# OpenLog.net
KiCad netlist of a schematic drawn in EAGLE
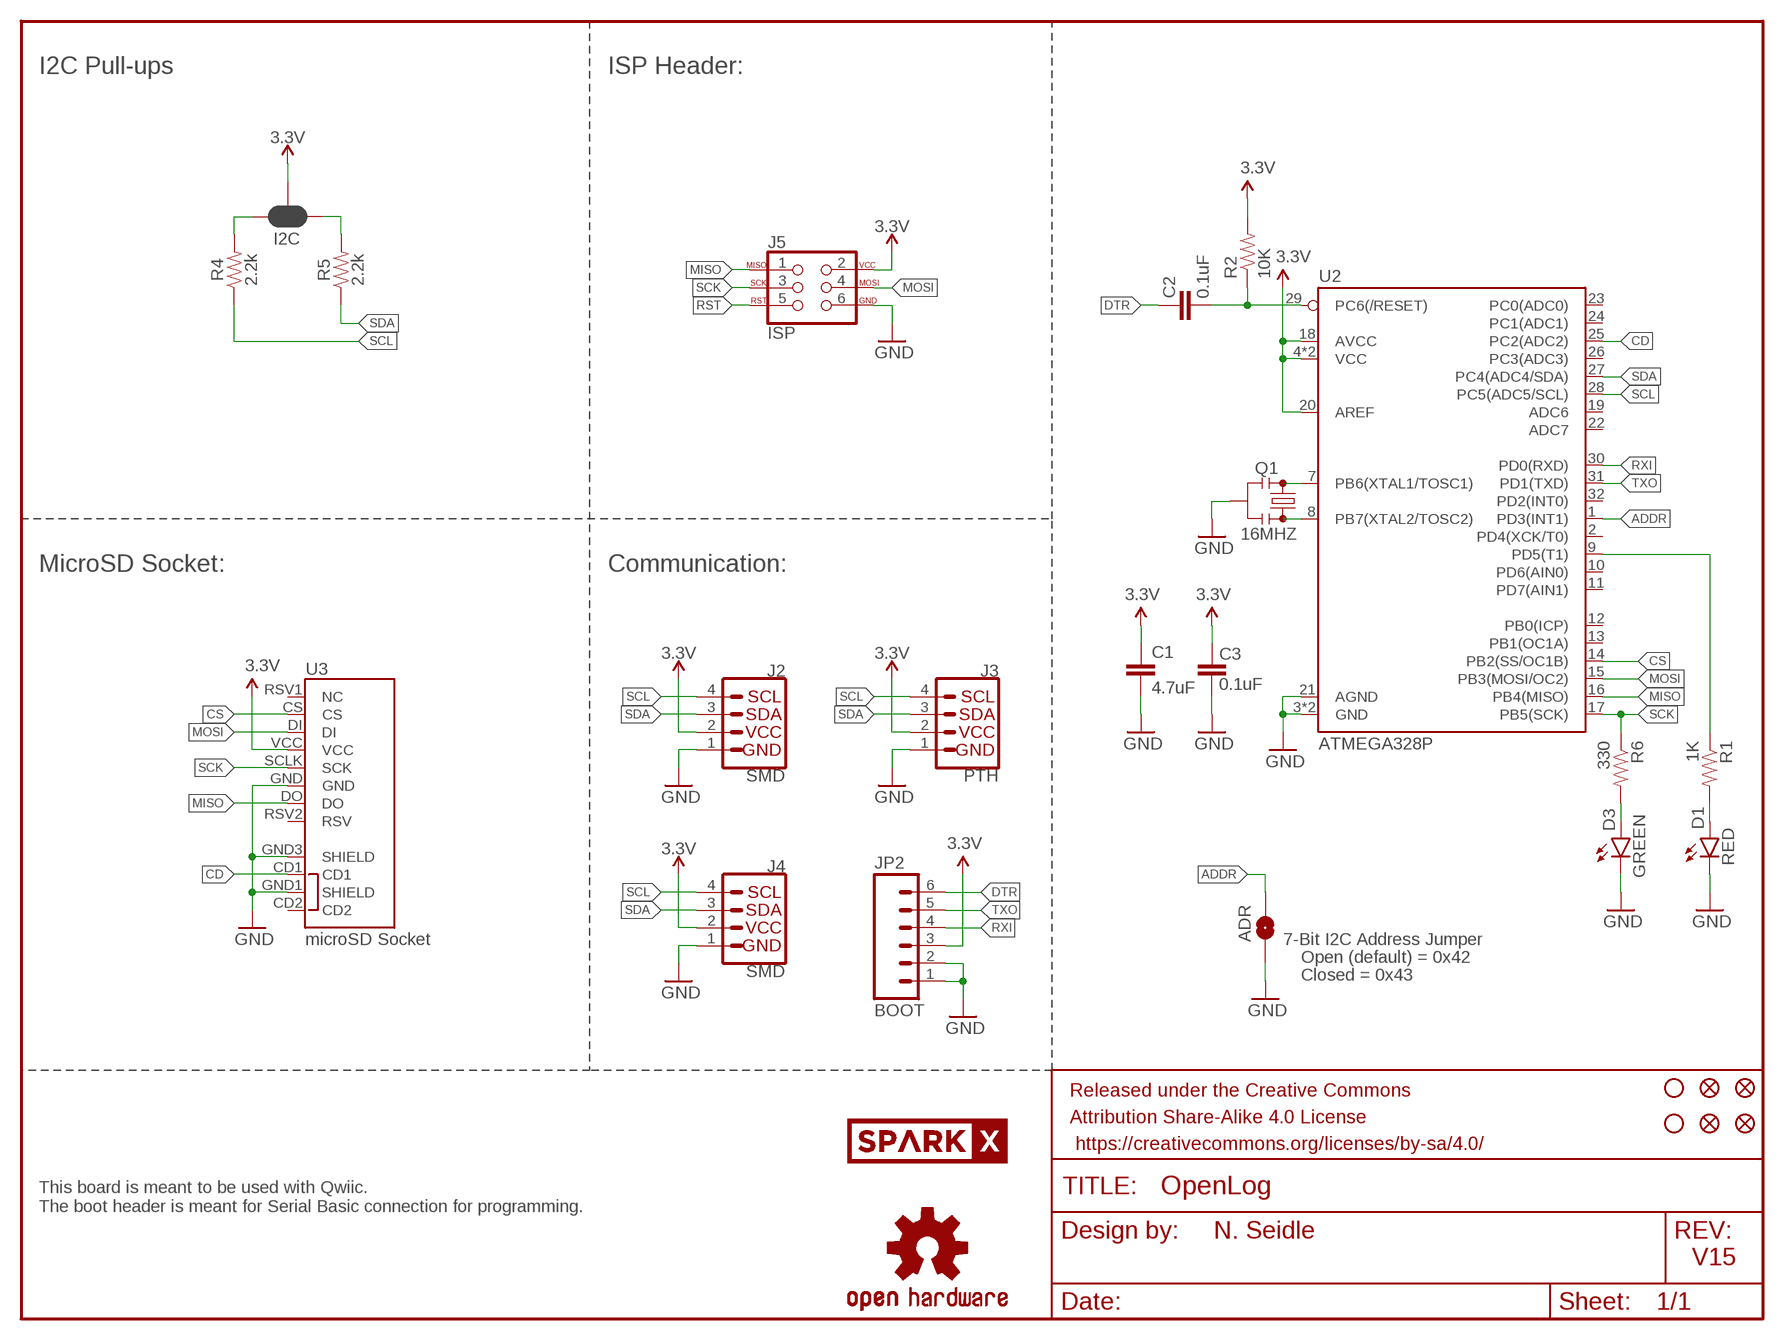
[diagram p0: schematic, sheet 1]

(export (version "E")
  (design (tool "Eeschema 10.0.6"))
  (components
    (comp (ref "ADR")
      (value "SOLDERJUMPERNO")
      (footprint "eagle-import:SJ_2S-NO")
      (libsource (lib "eagle-import") (part "SOLDERJUMPERNO"))
    )
    (comp (ref "C1")
      (value "4.7uF")
      (footprint "eagle-import:0603")
      (libsource (lib "eagle-import") (part "4.7UF0603"))
    )
    (comp (ref "C2")
      (value "0.1uF")
      (footprint "eagle-import:0603-CAP")
      (libsource (lib "eagle-import") (part "0.1UF-25V(+80/-20%)(0603)"))
    )
    (comp (ref "C3")
      (value "0.1uF")
      (footprint "eagle-import:0603-CAP")
      (libsource (lib "eagle-import") (part "0.1UF-25V(+80/-20%)(0603)"))
    )
    (comp (ref "D1")
      (value "RED")
      (footprint "eagle-import:LED-0603")
      (libsource (lib "eagle-import") (part "LED-RED0603"))
    )
    (comp (ref "D3")
      (value "GREEN")
      (footprint "eagle-import:LED-0603")
      (libsource (lib "eagle-import") (part "LED-GREEN0603"))
    )
    (comp (ref "FID1")
      (value "FIDUCIALUFIDUCIAL")
      (footprint "eagle-import:MICRO-FIDUCIAL")
      (libsource (lib "eagle-import") (part "FIDUCIALUFIDUCIAL"))
    )
    (comp (ref "FID2")
      (value "FIDUCIALUFIDUCIAL")
      (footprint "eagle-import:MICRO-FIDUCIAL")
      (libsource (lib "eagle-import") (part "FIDUCIALUFIDUCIAL"))
    )
    (comp (ref "FID3")
      (value "FIDUCIALUFIDUCIAL")
      (footprint "eagle-import:MICRO-FIDUCIAL")
      (libsource (lib "eagle-import") (part "FIDUCIALUFIDUCIAL"))
    )
    (comp (ref "FID4")
      (value "FIDUCIALUFIDUCIAL")
      (footprint "eagle-import:MICRO-FIDUCIAL")
      (libsource (lib "eagle-import") (part "FIDUCIALUFIDUCIAL"))
    )
    (comp (ref "FRAME1")
      (value "FRAME-LETTER")
      (footprint "eagle-import:CREATIVE_COMMONS")
      (libsource (lib "eagle-import") (part "FRAME-LETTER"))
    )
    (comp (ref "I2C")
      (value "JUMPER-SMT_3_2-NC_PASTE_SILK")
      (footprint "eagle-import:SMT-JUMPER_3_2-NC_PASTE_SILK")
      (libsource (lib "eagle-import") (part "JUMPER-SMT_3_2-NC_PASTE_SILK"))
    )
    (comp (ref "J2")
      (value "SMD")
      (footprint "eagle-import:1X04_1MM_RA")
      (libsource (lib "eagle-import") (part "QWIIC_CONNECTORJS-1MM"))
    )
    (comp (ref "J3")
      (value "PTH")
      (footprint "eagle-import:1X04_NO_SILK")
      (libsource (lib "eagle-import") (part "I2C_STANDARD_NO_SILK"))
    )
    (comp (ref "J4")
      (value "SMD")
      (footprint "eagle-import:1X04_1MM_RA")
      (libsource (lib "eagle-import") (part "QWIIC_CONNECTORJS-1MM"))
    )
    (comp (ref "J5")
      (value "ISP")
      (footprint "eagle-import:2X3_TEST_POINTS")
      (libsource (lib "eagle-import") (part "AVR_SPI_PROG_3X2TESTPOINTS"))
    )
    (comp (ref "JP2")
      (value "BOOT")
      (footprint "eagle-import:1X06_NO_SILK")
      (libsource (lib "eagle-import") (part "M06NO_SILK_FEMALE_PTH"))
    )
    (comp (ref "JP3")
      (value "STAND-OFF")
      (footprint "eagle-import:STAND-OFF")
      (libsource (lib "eagle-import") (part "STAND-OFF"))
    )
    (comp (ref "JP4")
      (value "STAND-OFF")
      (footprint "eagle-import:STAND-OFF")
      (libsource (lib "eagle-import") (part "STAND-OFF"))
    )
    (comp (ref "LOGO2")
      (value "OSHW-LOGOMINI")
      (footprint "eagle-import:OSHW-LOGO-MINI")
      (libsource (lib "eagle-import") (part "OSHW-LOGOMINI"))
    )
    (comp (ref "Q1")
      (value "16MHZ")
      (footprint "eagle-import:RESONATOR-SMD")
      (libsource (lib "eagle-import") (part "RESONATOR16MHZ"))
    )
    (comp (ref "R1")
      (value "1K")
      (footprint "eagle-import:0603-RES")
      (libsource (lib "eagle-import") (part "1KOHM-1/10W-1%(0603)"))
    )
    (comp (ref "R2")
      (value "10K")
      (footprint "eagle-import:0603-RES")
      (libsource (lib "eagle-import") (part "10KOHM-1/10W-1%(0603)0603"))
    )
    (comp (ref "R4")
      (value "2.2k")
      (footprint "eagle-import:0603")
      (libsource (lib "eagle-import") (part "2.2KOHM-0603-1/10W-1%"))
    )
    (comp (ref "R5")
      (value "2.2k")
      (footprint "eagle-import:0603")
      (libsource (lib "eagle-import") (part "2.2KOHM-0603-1/10W-1%"))
    )
    (comp (ref "R6")
      (value "330")
      (footprint "eagle-import:0603-RES")
      (libsource (lib "eagle-import") (part "330OHM1/10W1%(0603)"))
    )
    (comp (ref "U$1")
      (value "SPARKX-LOGO4")
      (footprint "eagle-import:SPARKX-MEDIUM")
      (libsource (lib "eagle-import") (part "SPARKX-LOGO4"))
    )
    (comp (ref "U$2")
      (value "SPARKX-LOGO3")
      (footprint "eagle-import:SPARKX-SMALL")
      (libsource (lib "eagle-import") (part "SPARKX-LOGO3"))
    )
    (comp (ref "U2")
      (value "ATMEGA328P")
      (footprint "eagle-import:TQFP32-08")
      (libsource (lib "eagle-import") (part "ATMEGA328P_TQFP"))
    )
    (comp (ref "U3")
      (value "microSD Socket")
      (footprint "eagle-import:MICRO-SD-SOCKET-PP")
      (libsource (lib "eagle-import") (part "MICRO_SD_SOCKETNEW"))
    )
  )
  (nets
    (net (code "1") (name "3.3V") (class "Default")
      (node (ref "C1") (pin "1") (pinfunction "1_1") (pintype "passive"))
      (node (ref "C3") (pin "2") (pinfunction "2_2") (pintype "passive"))
      (node (ref "I2C") (pin "2") (pinfunction "2_2") (pintype "passive"))
      (node (ref "J2") (pin "2") (pinfunction "2_2") (pintype "power_in"))
      (node (ref "J3") (pin "2") (pinfunction "VCC_2") (pintype "power_in"))
      (node (ref "J4") (pin "2") (pinfunction "2_2") (pintype "power_in"))
      (node (ref "J5") (pin "2") (pinfunction "2_2") (pintype "passive"))
      (node (ref "JP2") (pin "3") (pinfunction "3_3") (pintype "passive"))
      (node (ref "R2") (pin "2") (pinfunction "2_2") (pintype "passive"))
      (node (ref "U2") (pin "18") (pinfunction "AVCC_18") (pintype "bidirectional"))
      (node (ref "U2") (pin "20") (pinfunction "AREF_20") (pintype "bidirectional"))
      (node (ref "U2") (pin "4") (pinfunction "VCC_4") (pintype "bidirectional"))
      (node (ref "U2") (pin "6") (pinfunction "VCC_6") (pintype "bidirectional"))
      (node (ref "U3") (pin "VCC") (pinfunction "VCC_VCC") (pintype "bidirectional"))
    )
    (net (code "2") (name "ADDR") (class "Default")
      (node (ref "ADR") (pin "2") (pinfunction "2_2") (pintype "passive"))
      (node (ref "U2") (pin "1") (pinfunction "PD3(INT1)_1") (pintype "bidirectional"))
    )
    (net (code "3") (name "CD") (class "Default")
      (node (ref "U2") (pin "25") (pinfunction "PC2(ADC2)_25") (pintype "bidirectional"))
      (node (ref "U3") (pin "CD1") (pinfunction "CD1_CD1") (pintype "bidirectional"))
    )
    (net (code "4") (name "CS") (class "Default")
      (node (ref "U2") (pin "14") (pinfunction "PB2(SS/OC1B)_14") (pintype "bidirectional"))
      (node (ref "U3") (pin "CS") (pinfunction "CS_CS") (pintype "bidirectional"))
    )
    (net (code "5") (name "DTR") (class "Default")
      (node (ref "C2") (pin "2") (pinfunction "2_2") (pintype "passive"))
      (node (ref "JP2") (pin "6") (pinfunction "6_6") (pintype "passive"))
    )
    (net (code "6") (name "GND") (class "Default")
      (node (ref "ADR") (pin "1") (pinfunction "1_1") (pintype "passive"))
      (node (ref "C1") (pin "2") (pinfunction "2_2") (pintype "passive"))
      (node (ref "C3") (pin "1") (pinfunction "1_1") (pintype "passive"))
      (node (ref "D1") (pin "C") (pinfunction "C_C") (pintype "passive"))
      (node (ref "D3") (pin "C") (pinfunction "C_C") (pintype "passive"))
      (node (ref "J2") (pin "1") (pinfunction "1_1") (pintype "power_in"))
      (node (ref "J3") (pin "1") (pinfunction "GND_1") (pintype "power_in"))
      (node (ref "J4") (pin "1") (pinfunction "1_1") (pintype "power_in"))
      (node (ref "J5") (pin "6") (pinfunction "6_6") (pintype "passive"))
      (node (ref "JP2") (pin "1") (pinfunction "1_1") (pintype "passive"))
      (node (ref "JP2") (pin "2") (pinfunction "2_2") (pintype "passive"))
      (node (ref "Q1") (pin "2") (pinfunction "2_2") (pintype "passive"))
      (node (ref "U2") (pin "21") (pinfunction "AGND_21") (pintype "bidirectional"))
      (node (ref "U2") (pin "3") (pinfunction "GND_3") (pintype "bidirectional"))
      (node (ref "U2") (pin "5") (pinfunction "GND_5") (pintype "bidirectional"))
      (node (ref "U3") (pin "GND") (pinfunction "GND_GND") (pintype "bidirectional"))
      (node (ref "U3") (pin "GND1") (pinfunction "SHIELD_GND1") (pintype "bidirectional"))
      (node (ref "U3") (pin "GND3") (pinfunction "SHIELD_GND3") (pintype "bidirectional"))
    )
    (net (code "7") (name "MISO") (class "Default")
      (node (ref "J5") (pin "1") (pinfunction "1_1") (pintype "passive"))
      (node (ref "U2") (pin "16") (pinfunction "PB4(MISO)_16") (pintype "bidirectional"))
      (node (ref "U3") (pin "DO") (pinfunction "DO_DO") (pintype "bidirectional"))
    )
    (net (code "8") (name "MOSI") (class "Default")
      (node (ref "J5") (pin "4") (pinfunction "4_4") (pintype "passive"))
      (node (ref "U2") (pin "15") (pinfunction "PB3(MOSI/OC2)_15") (pintype "bidirectional"))
      (node (ref "U3") (pin "DI") (pinfunction "DI_DI") (pintype "bidirectional"))
    )
    (net (code "9") (name "Net-(D1-PadA)") (class "Default")
      (node (ref "D1") (pin "A") (pinfunction "A_A") (pintype "passive"))
      (node (ref "R1") (pin "2") (pinfunction "2_2") (pintype "passive"))
    )
    (net (code "10") (name "Net-(D3-PadA)") (class "Default")
      (node (ref "D3") (pin "A") (pinfunction "A_A") (pintype "passive"))
      (node (ref "R6") (pin "2") (pinfunction "2_2") (pintype "passive"))
    )
    (net (code "11") (name "Net-(I2C-Pad1)") (class "Default")
      (node (ref "I2C") (pin "1") (pinfunction "1_1") (pintype "passive"))
      (node (ref "R5") (pin "2") (pinfunction "2_2") (pintype "passive"))
    )
    (net (code "12") (name "Net-(I2C-Pad3)") (class "Default")
      (node (ref "I2C") (pin "3") (pinfunction "3_3") (pintype "passive"))
      (node (ref "R4") (pin "2") (pinfunction "2_2") (pintype "passive"))
    )
    (net (code "13") (name "Net-(U2-PB6(XTAL1{slash}TOSC1))") (class "Default")
      (node (ref "Q1") (pin "3") (pinfunction "3_3") (pintype "passive"))
      (node (ref "U2") (pin "7") (pinfunction "PB6(XTAL1/TOSC1)_7") (pintype "bidirectional"))
    )
    (net (code "14") (name "Net-(U2-PB7(XTAL2{slash}TOSC2))") (class "Default")
      (node (ref "Q1") (pin "1") (pinfunction "1_1") (pintype "passive"))
      (node (ref "U2") (pin "8") (pinfunction "PB7(XTAL2/TOSC2)_8") (pintype "bidirectional"))
    )
    (net (code "15") (name "Net-(U2-PD5(T1))") (class "Default")
      (node (ref "R1") (pin "1") (pinfunction "1_1") (pintype "passive"))
      (node (ref "U2") (pin "9") (pinfunction "PD5(T1)_9") (pintype "bidirectional"))
    )
    (net (code "16") (name "RST") (class "Default")
      (node (ref "C2") (pin "1") (pinfunction "1_1") (pintype "passive"))
      (node (ref "J5") (pin "5") (pinfunction "5_5") (pintype "passive"))
      (node (ref "R2") (pin "1") (pinfunction "1_1") (pintype "passive"))
      (node (ref "U2") (pin "29") (pinfunction "PC6(/RESET)_29") (pintype "bidirectional"))
    )
    (net (code "17") (name "RXI") (class "Default")
      (node (ref "JP2") (pin "4") (pinfunction "4_4") (pintype "passive"))
      (node (ref "U2") (pin "30") (pinfunction "PD0(RXD)_30") (pintype "bidirectional"))
    )
    (net (code "18") (name "SCK") (class "Default")
      (node (ref "J5") (pin "3") (pinfunction "3_3") (pintype "passive"))
      (node (ref "R6") (pin "1") (pinfunction "1_1") (pintype "passive"))
      (node (ref "U2") (pin "17") (pinfunction "PB5(SCK)_17") (pintype "bidirectional"))
      (node (ref "U3") (pin "SCLK") (pinfunction "SCK_SCLK") (pintype "bidirectional"))
    )
    (net (code "19") (name "SCL") (class "Default")
      (node (ref "J2") (pin "4") (pinfunction "4_4") (pintype "passive"))
      (node (ref "J3") (pin "4") (pinfunction "SCL_4") (pintype "passive"))
      (node (ref "J4") (pin "4") (pinfunction "4_4") (pintype "passive"))
      (node (ref "R4") (pin "1") (pinfunction "1_1") (pintype "passive"))
      (node (ref "U2") (pin "28") (pinfunction "PC5(ADC5/SCL)_28") (pintype "bidirectional"))
    )
    (net (code "20") (name "SDA") (class "Default")
      (node (ref "J2") (pin "3") (pinfunction "3_3") (pintype "passive"))
      (node (ref "J3") (pin "3") (pinfunction "SDA_3") (pintype "passive"))
      (node (ref "J4") (pin "3") (pinfunction "3_3") (pintype "passive"))
      (node (ref "R5") (pin "1") (pinfunction "1_1") (pintype "passive"))
      (node (ref "U2") (pin "27") (pinfunction "PC4(ADC4/SDA)_27") (pintype "bidirectional"))
    )
    (net (code "21") (name "TXO") (class "Default")
      (node (ref "JP2") (pin "5") (pinfunction "5_5") (pintype "passive"))
      (node (ref "U2") (pin "31") (pinfunction "PD1(TXD)_31") (pintype "bidirectional"))
    )
    (net (code "22") (name "unconnected-(U2-ADC6-Pad19)") (class "Default")
      (node (ref "U2") (pin "19") (pinfunction "ADC6_19") (pintype "bidirectional"))
    )
    (net (code "23") (name "unconnected-(U2-ADC7-Pad22)") (class "Default")
      (node (ref "U2") (pin "22") (pinfunction "ADC7_22") (pintype "bidirectional"))
    )
    (net (code "24") (name "unconnected-(U2-PB0(ICP)-Pad12)") (class "Default")
      (node (ref "U2") (pin "12") (pinfunction "PB0(ICP)_12") (pintype "bidirectional"))
    )
    (net (code "25") (name "unconnected-(U2-PB1(OC1A)-Pad13)") (class "Default")
      (node (ref "U2") (pin "13") (pinfunction "PB1(OC1A)_13") (pintype "bidirectional"))
    )
    (net (code "26") (name "unconnected-(U2-PC0(ADC0)-Pad23)") (class "Default")
      (node (ref "U2") (pin "23") (pinfunction "PC0(ADC0)_23") (pintype "bidirectional"))
    )
    (net (code "27") (name "unconnected-(U2-PC1(ADC1)-Pad24)") (class "Default")
      (node (ref "U2") (pin "24") (pinfunction "PC1(ADC1)_24") (pintype "bidirectional"))
    )
    (net (code "28") (name "unconnected-(U2-PC3(ADC3)-Pad26)") (class "Default")
      (node (ref "U2") (pin "26") (pinfunction "PC3(ADC3)_26") (pintype "bidirectional"))
    )
    (net (code "29") (name "unconnected-(U2-PD2(INT0)-Pad32)") (class "Default")
      (node (ref "U2") (pin "32") (pinfunction "PD2(INT0)_32") (pintype "bidirectional"))
    )
    (net (code "30") (name "unconnected-(U2-PD4(XCK{slash}T0)-Pad2)") (class "Default")
      (node (ref "U2") (pin "2") (pinfunction "PD4(XCK/T0)_2") (pintype "bidirectional"))
    )
    (net (code "31") (name "unconnected-(U2-PD6(AIN0)-Pad10)") (class "Default")
      (node (ref "U2") (pin "10") (pinfunction "PD6(AIN0)_10") (pintype "bidirectional"))
    )
    (net (code "32") (name "unconnected-(U2-PD7(AIN1)-Pad11)") (class "Default")
      (node (ref "U2") (pin "11") (pinfunction "PD7(AIN1)_11") (pintype "bidirectional"))
    )
    (net (code "33") (name "unconnected-(U3-NC-PadRSV1)") (class "Default")
      (node (ref "U3") (pin "RSV1") (pinfunction "NC_RSV1") (pintype "bidirectional"))
    )
    (net (code "34") (name "unconnected-(U3-PadCD2)") (class "Default")
      (node (ref "U3") (pin "CD2") (pinfunction "CD2_CD2") (pintype "bidirectional"))
    )
    (net (code "35") (name "unconnected-(U3-RSV-PadRSV2)") (class "Default")
      (node (ref "U3") (pin "RSV2") (pinfunction "RSV_RSV2") (pintype "bidirectional"))
    )
  )
)
